# snc98_3x4_Switch-futuba.net
KiCad netlist of a schematic drawn in EAGLE
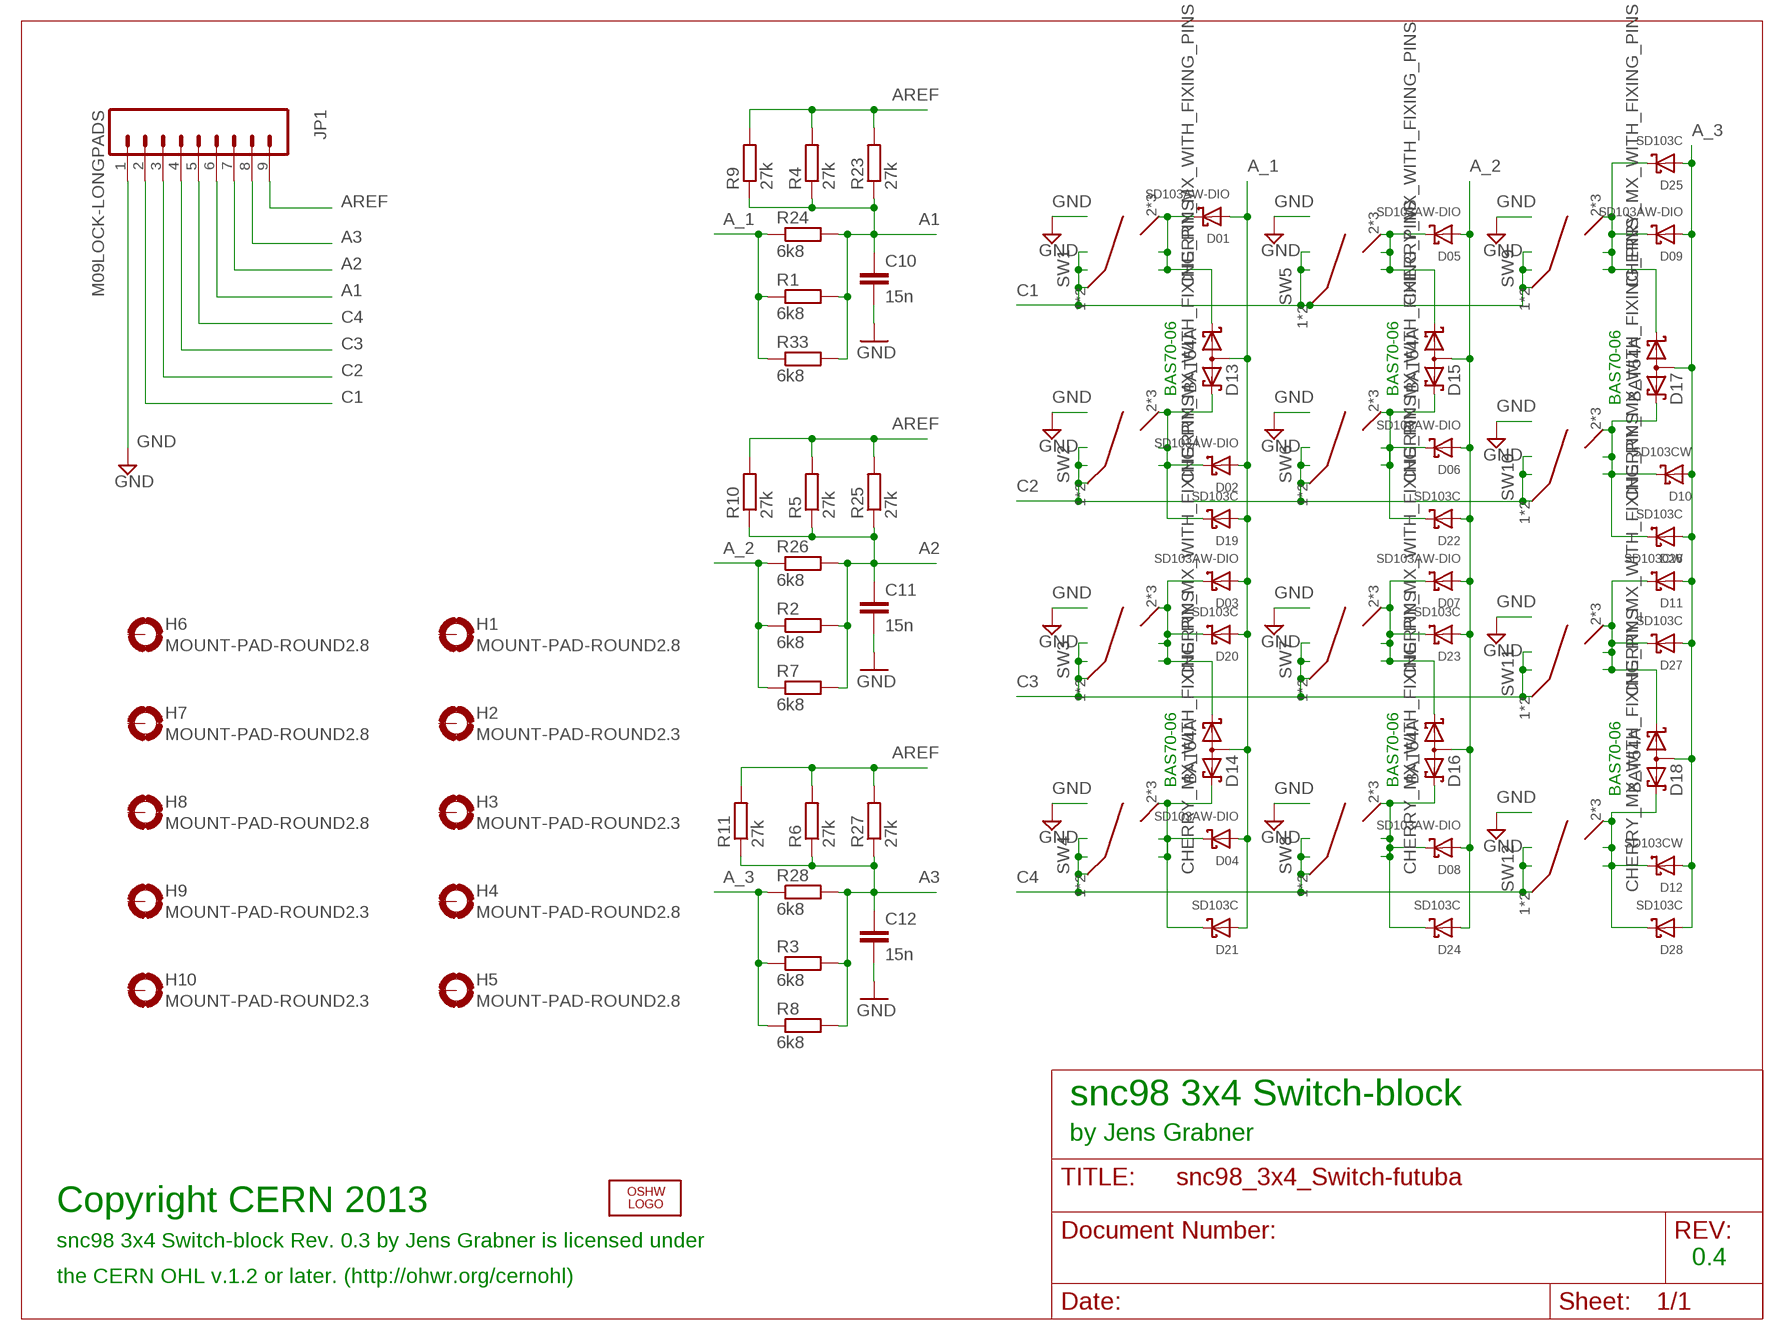
[diagram p0: schematic, sheet 1]

(export (version "E")
  (design (tool "Eeschema 10.0.6"))
  (components
    (comp (ref "C10")
      (value "15n")
      (footprint "eagle-import:C1206K")
      (libsource (lib "eagle-import") (part "C-EUC1206K"))
    )
    (comp (ref "C11")
      (value "15n")
      (footprint "eagle-import:C1206K")
      (libsource (lib "eagle-import") (part "C-EUC1206K"))
    )
    (comp (ref "C12")
      (value "15n")
      (footprint "eagle-import:C1206K")
      (libsource (lib "eagle-import") (part "C-EUC1206K"))
    )
    (comp (ref "D01")
      (value "SD103AW-DIO")
      (footprint "eagle-import:SOD-123F")
      (fields (field (name "MF") "MULTICOMP") (field (name "MPN") "SD103CW-7-F"))
      (libsource (lib "eagle-import") (part "DIODESOD-123F"))
    )
    (comp (ref "D02")
      (value "SD103AW-DIO")
      (footprint "eagle-import:SOD-123F")
      (fields (field (name "MF") "MULTICOMP") (field (name "MPN") "SD103CW-7-F"))
      (libsource (lib "eagle-import") (part "DIODESOD-123F"))
    )
    (comp (ref "D03")
      (value "SD103AW-DIO")
      (footprint "eagle-import:SOD-123F")
      (fields (field (name "MF") "MULTICOMP") (field (name "MPN") "SD103CW-7-F"))
      (libsource (lib "eagle-import") (part "DIODESOD-123F"))
    )
    (comp (ref "D04")
      (value "SD103AW-DIO")
      (footprint "eagle-import:SOD-123F")
      (fields (field (name "MF") "MULTICOMP") (field (name "MPN") "SD103CW-7-F"))
      (libsource (lib "eagle-import") (part "DIODESOD-123F"))
    )
    (comp (ref "D05")
      (value "SD103AW-DIO")
      (footprint "eagle-import:SOD-123F")
      (fields (field (name "MF") "MULTICOMP") (field (name "MPN") "SD103CW-7-F"))
      (libsource (lib "eagle-import") (part "DIODESOD-123F"))
    )
    (comp (ref "D06")
      (value "SD103AW-DIO")
      (footprint "eagle-import:SOD-123F")
      (fields (field (name "MF") "MULTICOMP") (field (name "MPN") "SD103CW-7-F"))
      (libsource (lib "eagle-import") (part "DIODESOD-123F"))
    )
    (comp (ref "D07")
      (value "SD103AW-DIO")
      (footprint "eagle-import:SOD-123F")
      (fields (field (name "MF") "MULTICOMP") (field (name "MPN") "SD103CW-7-F"))
      (libsource (lib "eagle-import") (part "DIODESOD-123F"))
    )
    (comp (ref "D08")
      (value "SD103AW-DIO")
      (footprint "eagle-import:SOD-123F")
      (fields (field (name "MF") "MULTICOMP") (field (name "MPN") "SD103CW-7-F"))
      (libsource (lib "eagle-import") (part "DIODESOD-123F"))
    )
    (comp (ref "D09")
      (value "SD103AW-DIO")
      (footprint "eagle-import:SOD-123F")
      (fields (field (name "MF") "MULTICOMP") (field (name "MPN") "SD103CW-7-F"))
      (libsource (lib "eagle-import") (part "DIODESOD-123F"))
    )
    (comp (ref "D10")
      (value "SD103CW")
      (footprint "eagle-import:SOD-123F")
      (fields (field (name "MF") "MULTICOMP") (field (name "MPN") "SD103CW-7-F"))
      (libsource (lib "eagle-import") (part "DIODESOD-123F"))
    )
    (comp (ref "D11")
      (value "SD103CW")
      (footprint "eagle-import:SOD-123F")
      (fields (field (name "MF") "MULTICOMP") (field (name "MPN") "SD103CW-7-F"))
      (libsource (lib "eagle-import") (part "DIODESOD-123F"))
    )
    (comp (ref "D12")
      (value "SD103CW")
      (footprint "eagle-import:SOD-123F")
      (fields (field (name "MF") "MULTICOMP") (field (name "MPN") "SD103CW-7-F"))
      (libsource (lib "eagle-import") (part "DIODESOD-123F"))
    )
    (comp (ref "D13")
      (value "BAT54A")
      (footprint "eagle-import:SOT23")
      (libsource (lib "eagle-import") (part "BAT54A"))
    )
    (comp (ref "D14")
      (value "BAT54A")
      (footprint "eagle-import:SOT23")
      (libsource (lib "eagle-import") (part "BAT54A"))
    )
    (comp (ref "D15")
      (value "BAT54A")
      (footprint "eagle-import:SOT23")
      (libsource (lib "eagle-import") (part "BAT54A"))
    )
    (comp (ref "D16")
      (value "BAT54A")
      (footprint "eagle-import:SOT23")
      (libsource (lib "eagle-import") (part "BAT54A"))
    )
    (comp (ref "D17")
      (value "BAT54A")
      (footprint "eagle-import:SOT23")
      (libsource (lib "eagle-import") (part "BAT54A"))
    )
    (comp (ref "D18")
      (value "BAT54A")
      (footprint "eagle-import:SOT23")
      (libsource (lib "eagle-import") (part "BAT54A"))
    )
    (comp (ref "D19")
      (value "SD103C")
      (footprint "eagle-import:280MIL-TH")
      (fields (field (name "MF") "MULTICOMP") (field (name "MPN") "SD103CW-7-F"))
      (libsource (lib "eagle-import") (part "DIODE280MIL-TH"))
    )
    (comp (ref "D20")
      (value "SD103C")
      (footprint "eagle-import:280MIL-TH")
      (fields (field (name "MF") "MULTICOMP") (field (name "MPN") "SD103CW-7-F"))
      (libsource (lib "eagle-import") (part "DIODE280MIL-TH"))
    )
    (comp (ref "D21")
      (value "SD103C")
      (footprint "eagle-import:280MIL-TH")
      (fields (field (name "MF") "MULTICOMP") (field (name "MPN") "SD103CW-7-F"))
      (libsource (lib "eagle-import") (part "DIODE280MIL-TH"))
    )
    (comp (ref "D22")
      (value "SD103C")
      (footprint "eagle-import:280MIL-TH")
      (fields (field (name "MF") "MULTICOMP") (field (name "MPN") "SD103CW-7-F"))
      (libsource (lib "eagle-import") (part "DIODE280MIL-TH"))
    )
    (comp (ref "D23")
      (value "SD103C")
      (footprint "eagle-import:280MIL-TH")
      (fields (field (name "MF") "MULTICOMP") (field (name "MPN") "SD103CW-7-F"))
      (libsource (lib "eagle-import") (part "DIODE280MIL-TH"))
    )
    (comp (ref "D24")
      (value "SD103C")
      (footprint "eagle-import:280MIL-TH")
      (fields (field (name "MF") "MULTICOMP") (field (name "MPN") "SD103CW-7-F"))
      (libsource (lib "eagle-import") (part "DIODE280MIL-TH"))
    )
    (comp (ref "D25")
      (value "SD103C")
      (footprint "eagle-import:280MIL-TH")
      (fields (field (name "MF") "MULTICOMP") (field (name "MPN") "SD103CW-7-F"))
      (libsource (lib "eagle-import") (part "DIODE280MIL-TH"))
    )
    (comp (ref "D26")
      (value "SD103C")
      (footprint "eagle-import:280MIL-TH")
      (fields (field (name "MF") "MULTICOMP") (field (name "MPN") "SD103CW-7-F"))
      (libsource (lib "eagle-import") (part "DIODE280MIL-TH"))
    )
    (comp (ref "D27")
      (value "SD103C")
      (footprint "eagle-import:280MIL-TH")
      (fields (field (name "MF") "MULTICOMP") (field (name "MPN") "SD103CW-7-F"))
      (libsource (lib "eagle-import") (part "DIODE280MIL-TH"))
    )
    (comp (ref "D28")
      (value "SD103C")
      (footprint "eagle-import:280MIL-TH")
      (fields (field (name "MF") "MULTICOMP") (field (name "MPN") "SD103CW-7-F"))
      (libsource (lib "eagle-import") (part "DIODE280MIL-TH"))
    )
    (comp (ref "H1")
      (value "MOUNT-PAD-ROUND2.8")
      (footprint "eagle-import:2,8-PAD")
      (libsource (lib "eagle-import") (part "MOUNT-PAD-ROUND2.8"))
    )
    (comp (ref "H2")
      (value "MOUNT-PAD-ROUND2.3")
      (footprint "eagle-import:2,3-PAD")
      (libsource (lib "eagle-import") (part "MOUNT-PAD-ROUND2.3"))
    )
    (comp (ref "H3")
      (value "MOUNT-PAD-ROUND2.3")
      (footprint "eagle-import:2,3-PAD")
      (libsource (lib "eagle-import") (part "MOUNT-PAD-ROUND2.3"))
    )
    (comp (ref "H4")
      (value "MOUNT-PAD-ROUND2.8")
      (footprint "eagle-import:2,8-PAD")
      (libsource (lib "eagle-import") (part "MOUNT-PAD-ROUND2.8"))
    )
    (comp (ref "H5")
      (value "MOUNT-PAD-ROUND2.8")
      (footprint "eagle-import:2,8-PAD")
      (libsource (lib "eagle-import") (part "MOUNT-PAD-ROUND2.8"))
    )
    (comp (ref "H6")
      (value "MOUNT-PAD-ROUND2.8")
      (footprint "eagle-import:2,8-PAD")
      (libsource (lib "eagle-import") (part "MOUNT-PAD-ROUND2.8"))
    )
    (comp (ref "H7")
      (value "MOUNT-PAD-ROUND2.8")
      (footprint "eagle-import:2,8-PAD")
      (libsource (lib "eagle-import") (part "MOUNT-PAD-ROUND2.8"))
    )
    (comp (ref "H8")
      (value "MOUNT-PAD-ROUND2.8")
      (footprint "eagle-import:2,8-PAD")
      (libsource (lib "eagle-import") (part "MOUNT-PAD-ROUND2.8"))
    )
    (comp (ref "H9")
      (value "MOUNT-PAD-ROUND2.3")
      (footprint "eagle-import:2,3-PAD")
      (libsource (lib "eagle-import") (part "MOUNT-PAD-ROUND2.3"))
    )
    (comp (ref "H10")
      (value "MOUNT-PAD-ROUND2.3")
      (footprint "eagle-import:2,3-PAD")
      (libsource (lib "eagle-import") (part "MOUNT-PAD-ROUND2.3"))
    )
    (comp (ref "JP1")
      (value "M09LOCK-LONGPADS")
      (footprint "eagle-import:1X09_LOCK_LONGPADS")
      (libsource (lib "eagle-import") (part "M09LOCK-LONGPADS"))
    )
    (comp (ref "LOGO1")
      (value "OSHW_LOGO_8MILX0150-NT")
      (footprint "eagle-import:OSHW_8X150_NOTEXT")
      (libsource (lib "eagle-import") (part "OSHW_LOGO_8MILX0150-NT"))
    )
    (comp (ref "R1")
      (value "6k8")
      (footprint "eagle-import:R1206")
      (libsource (lib "eagle-import") (part "R-EU_R1206"))
    )
    (comp (ref "R2")
      (value "6k8")
      (footprint "eagle-import:R1206")
      (libsource (lib "eagle-import") (part "R-EU_R1206"))
    )
    (comp (ref "R3")
      (value "6k8")
      (footprint "eagle-import:R1206")
      (libsource (lib "eagle-import") (part "R-EU_R1206"))
    )
    (comp (ref "R4")
      (value "27k")
      (footprint "eagle-import:R1206")
      (libsource (lib "eagle-import") (part "R-EU_R1206"))
    )
    (comp (ref "R5")
      (value "27k")
      (footprint "eagle-import:R1206")
      (libsource (lib "eagle-import") (part "R-EU_R1206"))
    )
    (comp (ref "R6")
      (value "27k")
      (footprint "eagle-import:R1206")
      (libsource (lib "eagle-import") (part "R-EU_R1206"))
    )
    (comp (ref "R7")
      (value "6k8")
      (footprint "eagle-import:M0805")
      (libsource (lib "eagle-import") (part "R-EU_M0805"))
    )
    (comp (ref "R8")
      (value "6k8")
      (footprint "eagle-import:M0805")
      (libsource (lib "eagle-import") (part "R-EU_M0805"))
    )
    (comp (ref "R9")
      (value "27k")
      (footprint "eagle-import:M0805")
      (libsource (lib "eagle-import") (part "R-EU_M0805"))
    )
    (comp (ref "R10")
      (value "27k")
      (footprint "eagle-import:M0805")
      (libsource (lib "eagle-import") (part "R-EU_M0805"))
    )
    (comp (ref "R11")
      (value "27k")
      (footprint "eagle-import:M0805")
      (libsource (lib "eagle-import") (part "R-EU_M0805"))
    )
    (comp (ref "R23")
      (value "27k")
      (footprint "eagle-import:0204_5")
      (libsource (lib "eagle-import") (part "R-EU_0204/5"))
    )
    (comp (ref "R24")
      (value "6k8")
      (footprint "eagle-import:0204_5")
      (libsource (lib "eagle-import") (part "R-EU_0204/5"))
    )
    (comp (ref "R25")
      (value "27k")
      (footprint "eagle-import:0204_5")
      (libsource (lib "eagle-import") (part "R-EU_0204/5"))
    )
    (comp (ref "R26")
      (value "6k8")
      (footprint "eagle-import:0204_5")
      (libsource (lib "eagle-import") (part "R-EU_0204/5"))
    )
    (comp (ref "R27")
      (value "27k")
      (footprint "eagle-import:0204_5")
      (libsource (lib "eagle-import") (part "R-EU_0204/5"))
    )
    (comp (ref "R28")
      (value "6k8")
      (footprint "eagle-import:0204_5")
      (libsource (lib "eagle-import") (part "R-EU_0204/5"))
    )
    (comp (ref "R33")
      (value "6k8")
      (footprint "eagle-import:M0805")
      (libsource (lib "eagle-import") (part "R-EU_M0805"))
    )
    (comp (ref "SW1")
      (value "CHERRY_MX_WITH_FIXING_PINS")
      (footprint "eagle-import:MX1A-XXNW")
      (libsource (lib "eagle-import") (part "CHERRY_MX_WITH_FIXING_PINS"))
    )
    (comp (ref "SW2")
      (value "CHERRY_MX_WITH_FIXING_PINS")
      (footprint "eagle-import:MX1A-XXNW")
      (libsource (lib "eagle-import") (part "CHERRY_MX_WITH_FIXING_PINS"))
    )
    (comp (ref "SW3")
      (value "CHERRY_MX_WITH_FIXING_PINS")
      (footprint "eagle-import:MX1A-XXNW")
      (libsource (lib "eagle-import") (part "CHERRY_MX_WITH_FIXING_PINS"))
    )
    (comp (ref "SW4")
      (value "CHERRY_MX_WITH_FIXING_PINS")
      (footprint "eagle-import:MX1A-XXNW")
      (libsource (lib "eagle-import") (part "CHERRY_MX_WITH_FIXING_PINS"))
    )
    (comp (ref "SW5")
      (value "CHERRY_MX_WITH_FIXING_PINS")
      (footprint "eagle-import:MX1A-XXNW")
      (libsource (lib "eagle-import") (part "CHERRY_MX_WITH_FIXING_PINS"))
    )
    (comp (ref "SW6")
      (value "CHERRY_MX_WITH_FIXING_PINS")
      (footprint "eagle-import:MX1A-XXNW")
      (libsource (lib "eagle-import") (part "CHERRY_MX_WITH_FIXING_PINS"))
    )
    (comp (ref "SW7")
      (value "CHERRY_MX_WITH_FIXING_PINS")
      (footprint "eagle-import:MX1A-XXNW")
      (libsource (lib "eagle-import") (part "CHERRY_MX_WITH_FIXING_PINS"))
    )
    (comp (ref "SW8")
      (value "CHERRY_MX_WITH_FIXING_PINS")
      (footprint "eagle-import:MX1A-XXNW")
      (libsource (lib "eagle-import") (part "CHERRY_MX_WITH_FIXING_PINS"))
    )
    (comp (ref "SW9")
      (value "CHERRY_MX_WITH_FIXING_PINS")
      (footprint "eagle-import:MX1A-XXNW")
      (libsource (lib "eagle-import") (part "CHERRY_MX_WITH_FIXING_PINS"))
    )
    (comp (ref "SW10")
      (value "CHERRY_MX_WITH_FIXING_PINS")
      (footprint "eagle-import:MX1A-XXNW")
      (libsource (lib "eagle-import") (part "CHERRY_MX_WITH_FIXING_PINS"))
    )
    (comp (ref "SW11")
      (value "CHERRY_MX_WITH_FIXING_PINS")
      (footprint "eagle-import:MX1A-XXNW")
      (libsource (lib "eagle-import") (part "CHERRY_MX_WITH_FIXING_PINS"))
    )
    (comp (ref "SW12")
      (value "CHERRY_MX_WITH_FIXING_PINS")
      (footprint "eagle-import:MX1A-XXNW")
      (libsource (lib "eagle-import") (part "CHERRY_MX_WITH_FIXING_PINS"))
    )
  )
  (nets
    (net (code "1") (name "/A1") (class "Default")
      (node (ref "C10") (pin "1") (pinfunction "1_1") (pintype "passive"))
      (node (ref "JP1") (pin "6") (pinfunction "6_6") (pintype "passive"))
      (node (ref "R1") (pin "2") (pinfunction "2_2") (pintype "passive"))
      (node (ref "R23") (pin "1") (pinfunction "1_1") (pintype "passive"))
      (node (ref "R24") (pin "2") (pinfunction "2_2") (pintype "passive"))
      (node (ref "R33") (pin "2") (pinfunction "2_2") (pintype "passive"))
      (node (ref "R4") (pin "1") (pinfunction "1_1") (pintype "passive"))
      (node (ref "R9") (pin "1") (pinfunction "1_1") (pintype "passive"))
    )
    (net (code "2") (name "/A2") (class "Default")
      (node (ref "C11") (pin "1") (pinfunction "1_1") (pintype "passive"))
      (node (ref "JP1") (pin "7") (pinfunction "7_7") (pintype "passive"))
      (node (ref "R10") (pin "1") (pinfunction "1_1") (pintype "passive"))
      (node (ref "R2") (pin "2") (pinfunction "2_2") (pintype "passive"))
      (node (ref "R25") (pin "1") (pinfunction "1_1") (pintype "passive"))
      (node (ref "R26") (pin "2") (pinfunction "2_2") (pintype "passive"))
      (node (ref "R5") (pin "1") (pinfunction "1_1") (pintype "passive"))
      (node (ref "R7") (pin "2") (pinfunction "2_2") (pintype "passive"))
    )
    (net (code "3") (name "/A3") (class "Default")
      (node (ref "C12") (pin "1") (pinfunction "1_1") (pintype "passive"))
      (node (ref "JP1") (pin "8") (pinfunction "8_8") (pintype "passive"))
      (node (ref "R11") (pin "1") (pinfunction "1_1") (pintype "passive"))
      (node (ref "R27") (pin "1") (pinfunction "1_1") (pintype "passive"))
      (node (ref "R28") (pin "2") (pinfunction "2_2") (pintype "passive"))
      (node (ref "R3") (pin "2") (pinfunction "2_2") (pintype "passive"))
      (node (ref "R6") (pin "1") (pinfunction "1_1") (pintype "passive"))
      (node (ref "R8") (pin "2") (pinfunction "2_2") (pintype "passive"))
    )
    (net (code "4") (name "/AREF") (class "Default")
      (node (ref "JP1") (pin "9") (pinfunction "9_9") (pintype "passive"))
      (node (ref "R10") (pin "2") (pinfunction "2_2") (pintype "passive"))
      (node (ref "R11") (pin "2") (pinfunction "2_2") (pintype "passive"))
      (node (ref "R23") (pin "2") (pinfunction "2_2") (pintype "passive"))
      (node (ref "R25") (pin "2") (pinfunction "2_2") (pintype "passive"))
      (node (ref "R27") (pin "2") (pinfunction "2_2") (pintype "passive"))
      (node (ref "R4") (pin "2") (pinfunction "2_2") (pintype "passive"))
      (node (ref "R5") (pin "2") (pinfunction "2_2") (pintype "passive"))
      (node (ref "R6") (pin "2") (pinfunction "2_2") (pintype "passive"))
      (node (ref "R9") (pin "2") (pinfunction "2_2") (pintype "passive"))
    )
    (net (code "5") (name "/A_1") (class "Default")
      (node (ref "D01") (pin "A") (pinfunction "A_A") (pintype "passive"))
      (node (ref "D02") (pin "A") (pinfunction "A_A") (pintype "passive"))
      (node (ref "D03") (pin "A") (pinfunction "A_A") (pintype "passive"))
      (node (ref "D04") (pin "A") (pinfunction "A_A") (pintype "passive"))
      (node (ref "D13") (pin "3") (pinfunction "AA_3") (pintype "passive"))
      (node (ref "D14") (pin "3") (pinfunction "AA_3") (pintype "passive"))
      (node (ref "D19") (pin "P$1") (pinfunction "A_P$1") (pintype "passive"))
      (node (ref "D20") (pin "P$1") (pinfunction "A_P$1") (pintype "passive"))
      (node (ref "D21") (pin "P$1") (pinfunction "A_P$1") (pintype "passive"))
      (node (ref "R1") (pin "1") (pinfunction "1_1") (pintype "passive"))
      (node (ref "R24") (pin "1") (pinfunction "1_1") (pintype "passive"))
      (node (ref "R33") (pin "1") (pinfunction "1_1") (pintype "passive"))
    )
    (net (code "6") (name "/A_2") (class "Default")
      (node (ref "D05") (pin "A") (pinfunction "A_A") (pintype "passive"))
      (node (ref "D06") (pin "A") (pinfunction "A_A") (pintype "passive"))
      (node (ref "D07") (pin "A") (pinfunction "A_A") (pintype "passive"))
      (node (ref "D08") (pin "A") (pinfunction "A_A") (pintype "passive"))
      (node (ref "D15") (pin "3") (pinfunction "AA_3") (pintype "passive"))
      (node (ref "D16") (pin "3") (pinfunction "AA_3") (pintype "passive"))
      (node (ref "D22") (pin "P$1") (pinfunction "A_P$1") (pintype "passive"))
      (node (ref "D23") (pin "P$1") (pinfunction "A_P$1") (pintype "passive"))
      (node (ref "D24") (pin "P$1") (pinfunction "A_P$1") (pintype "passive"))
      (node (ref "R2") (pin "1") (pinfunction "1_1") (pintype "passive"))
      (node (ref "R26") (pin "1") (pinfunction "1_1") (pintype "passive"))
      (node (ref "R7") (pin "1") (pinfunction "1_1") (pintype "passive"))
    )
    (net (code "7") (name "/A_3") (class "Default")
      (node (ref "D09") (pin "A") (pinfunction "A_A") (pintype "passive"))
      (node (ref "D10") (pin "A") (pinfunction "A_A") (pintype "passive"))
      (node (ref "D11") (pin "A") (pinfunction "A_A") (pintype "passive"))
      (node (ref "D12") (pin "A") (pinfunction "A_A") (pintype "passive"))
      (node (ref "D17") (pin "3") (pinfunction "AA_3") (pintype "passive"))
      (node (ref "D18") (pin "3") (pinfunction "AA_3") (pintype "passive"))
      (node (ref "D25") (pin "P$1") (pinfunction "A_P$1") (pintype "passive"))
      (node (ref "D26") (pin "P$1") (pinfunction "A_P$1") (pintype "passive"))
      (node (ref "D27") (pin "P$1") (pinfunction "A_P$1") (pintype "passive"))
      (node (ref "D28") (pin "P$1") (pinfunction "A_P$1") (pintype "passive"))
      (node (ref "R28") (pin "1") (pinfunction "1_1") (pintype "passive"))
      (node (ref "R3") (pin "1") (pinfunction "1_1") (pintype "passive"))
      (node (ref "R8") (pin "1") (pinfunction "1_1") (pintype "passive"))
    )
    (net (code "8") (name "/C1") (class "Default")
      (node (ref "JP1") (pin "2") (pinfunction "2_2") (pintype "passive"))
      (node (ref "SW1") (pin "1") (pinfunction "1_1") (pintype "passive"))
      (node (ref "SW1") (pin "3") (pinfunction "1_3") (pintype "passive"))
      (node (ref "SW5") (pin "1") (pinfunction "1_1") (pintype "passive"))
      (node (ref "SW5") (pin "3") (pinfunction "1_3") (pintype "passive"))
      (node (ref "SW9") (pin "1") (pinfunction "1_1") (pintype "passive"))
      (node (ref "SW9") (pin "3") (pinfunction "1_3") (pintype "passive"))
    )
    (net (code "9") (name "/C2") (class "Default")
      (node (ref "JP1") (pin "3") (pinfunction "3_3") (pintype "passive"))
      (node (ref "SW10") (pin "1") (pinfunction "1_1") (pintype "passive"))
      (node (ref "SW10") (pin "3") (pinfunction "1_3") (pintype "passive"))
      (node (ref "SW2") (pin "1") (pinfunction "1_1") (pintype "passive"))
      (node (ref "SW2") (pin "3") (pinfunction "1_3") (pintype "passive"))
      (node (ref "SW6") (pin "1") (pinfunction "1_1") (pintype "passive"))
      (node (ref "SW6") (pin "3") (pinfunction "1_3") (pintype "passive"))
    )
    (net (code "10") (name "/C3") (class "Default")
      (node (ref "JP1") (pin "4") (pinfunction "4_4") (pintype "passive"))
      (node (ref "SW11") (pin "1") (pinfunction "1_1") (pintype "passive"))
      (node (ref "SW11") (pin "3") (pinfunction "1_3") (pintype "passive"))
      (node (ref "SW3") (pin "1") (pinfunction "1_1") (pintype "passive"))
      (node (ref "SW3") (pin "3") (pinfunction "1_3") (pintype "passive"))
      (node (ref "SW7") (pin "1") (pinfunction "1_1") (pintype "passive"))
      (node (ref "SW7") (pin "3") (pinfunction "1_3") (pintype "passive"))
    )
    (net (code "11") (name "/C4") (class "Default")
      (node (ref "JP1") (pin "5") (pinfunction "5_5") (pintype "passive"))
      (node (ref "SW12") (pin "1") (pinfunction "1_1") (pintype "passive"))
      (node (ref "SW12") (pin "3") (pinfunction "1_3") (pintype "passive"))
      (node (ref "SW4") (pin "1") (pinfunction "1_1") (pintype "passive"))
      (node (ref "SW4") (pin "3") (pinfunction "1_3") (pintype "passive"))
      (node (ref "SW8") (pin "1") (pinfunction "1_1") (pintype "passive"))
      (node (ref "SW8") (pin "3") (pinfunction "1_3") (pintype "passive"))
    )
    (net (code "12") (name "GND") (class "Default")
      (node (ref "C10") (pin "2") (pinfunction "2_2") (pintype "passive"))
      (node (ref "C11") (pin "2") (pinfunction "2_2") (pintype "passive"))
      (node (ref "C12") (pin "2") (pinfunction "2_2") (pintype "passive"))
      (node (ref "JP1") (pin "1") (pinfunction "1_1") (pintype "passive"))
    )
    (net (code "13") (name "Net-(D13-K1)") (class "Default")
      (node (ref "D01") (pin "C") (pinfunction "C_C") (pintype "passive"))
      (node (ref "D13") (pin "1") (pinfunction "K1_1") (pintype "passive"))
      (node (ref "SW1") (pin "2") (pinfunction "2_2") (pintype "passive"))
      (node (ref "SW1") (pin "4") (pinfunction "2_4") (pintype "passive"))
      (node (ref "SW1") (pin "5") (pinfunction "2_5") (pintype "passive"))
    )
    (net (code "14") (name "Net-(D13-K2)") (class "Default")
      (node (ref "D02") (pin "C") (pinfunction "C_C") (pintype "passive"))
      (node (ref "D13") (pin "2") (pinfunction "K2_2") (pintype "passive"))
      (node (ref "D19") (pin "P$2") (pinfunction "C_P$2") (pintype "passive"))
      (node (ref "SW2") (pin "2") (pinfunction "2_2") (pintype "passive"))
      (node (ref "SW2") (pin "4") (pinfunction "2_4") (pintype "passive"))
      (node (ref "SW2") (pin "5") (pinfunction "2_5") (pintype "passive"))
    )
    (net (code "15") (name "Net-(D14-K1)") (class "Default")
      (node (ref "D03") (pin "C") (pinfunction "C_C") (pintype "passive"))
      (node (ref "D14") (pin "1") (pinfunction "K1_1") (pintype "passive"))
      (node (ref "D20") (pin "P$2") (pinfunction "C_P$2") (pintype "passive"))
      (node (ref "SW3") (pin "2") (pinfunction "2_2") (pintype "passive"))
      (node (ref "SW3") (pin "4") (pinfunction "2_4") (pintype "passive"))
      (node (ref "SW3") (pin "5") (pinfunction "2_5") (pintype "passive"))
    )
    (net (code "16") (name "Net-(D14-K2)") (class "Default")
      (node (ref "D04") (pin "C") (pinfunction "C_C") (pintype "passive"))
      (node (ref "D14") (pin "2") (pinfunction "K2_2") (pintype "passive"))
      (node (ref "D21") (pin "P$2") (pinfunction "C_P$2") (pintype "passive"))
      (node (ref "SW4") (pin "2") (pinfunction "2_2") (pintype "passive"))
      (node (ref "SW4") (pin "4") (pinfunction "2_4") (pintype "passive"))
      (node (ref "SW4") (pin "5") (pinfunction "2_5") (pintype "passive"))
    )
    (net (code "17") (name "Net-(D15-K1)") (class "Default")
      (node (ref "D05") (pin "C") (pinfunction "C_C") (pintype "passive"))
      (node (ref "D15") (pin "1") (pinfunction "K1_1") (pintype "passive"))
      (node (ref "SW5") (pin "2") (pinfunction "2_2") (pintype "passive"))
      (node (ref "SW5") (pin "4") (pinfunction "2_4") (pintype "passive"))
      (node (ref "SW5") (pin "5") (pinfunction "2_5") (pintype "passive"))
    )
    (net (code "18") (name "Net-(D15-K2)") (class "Default")
      (node (ref "D06") (pin "C") (pinfunction "C_C") (pintype "passive"))
      (node (ref "D15") (pin "2") (pinfunction "K2_2") (pintype "passive"))
      (node (ref "D22") (pin "P$2") (pinfunction "C_P$2") (pintype "passive"))
      (node (ref "SW6") (pin "2") (pinfunction "2_2") (pintype "passive"))
      (node (ref "SW6") (pin "4") (pinfunction "2_4") (pintype "passive"))
      (node (ref "SW6") (pin "5") (pinfunction "2_5") (pintype "passive"))
    )
    (net (code "19") (name "Net-(D16-K1)") (class "Default")
      (node (ref "D07") (pin "C") (pinfunction "C_C") (pintype "passive"))
      (node (ref "D16") (pin "1") (pinfunction "K1_1") (pintype "passive"))
      (node (ref "D23") (pin "P$2") (pinfunction "C_P$2") (pintype "passive"))
      (node (ref "SW7") (pin "2") (pinfunction "2_2") (pintype "passive"))
      (node (ref "SW7") (pin "4") (pinfunction "2_4") (pintype "passive"))
      (node (ref "SW7") (pin "5") (pinfunction "2_5") (pintype "passive"))
    )
    (net (code "20") (name "Net-(D16-K2)") (class "Default")
      (node (ref "D08") (pin "C") (pinfunction "C_C") (pintype "passive"))
      (node (ref "D16") (pin "2") (pinfunction "K2_2") (pintype "passive"))
      (node (ref "D24") (pin "P$2") (pinfunction "C_P$2") (pintype "passive"))
      (node (ref "SW8") (pin "2") (pinfunction "2_2") (pintype "passive"))
      (node (ref "SW8") (pin "4") (pinfunction "2_4") (pintype "passive"))
      (node (ref "SW8") (pin "5") (pinfunction "2_5") (pintype "passive"))
    )
    (net (code "21") (name "Net-(D17-K1)") (class "Default")
      (node (ref "D09") (pin "C") (pinfunction "C_C") (pintype "passive"))
      (node (ref "D17") (pin "1") (pinfunction "K1_1") (pintype "passive"))
      (node (ref "D25") (pin "P$2") (pinfunction "C_P$2") (pintype "passive"))
      (node (ref "SW9") (pin "2") (pinfunction "2_2") (pintype "passive"))
      (node (ref "SW9") (pin "4") (pinfunction "2_4") (pintype "passive"))
      (node (ref "SW9") (pin "5") (pinfunction "2_5") (pintype "passive"))
    )
    (net (code "22") (name "Net-(D17-K2)") (class "Default")
      (node (ref "D10") (pin "C") (pinfunction "C_C") (pintype "passive"))
      (node (ref "D17") (pin "2") (pinfunction "K2_2") (pintype "passive"))
      (node (ref "D26") (pin "P$2") (pinfunction "C_P$2") (pintype "passive"))
      (node (ref "SW10") (pin "2") (pinfunction "2_2") (pintype "passive"))
      (node (ref "SW10") (pin "4") (pinfunction "2_4") (pintype "passive"))
      (node (ref "SW10") (pin "5") (pinfunction "2_5") (pintype "passive"))
    )
    (net (code "23") (name "Net-(D18-K1)") (class "Default")
      (node (ref "D11") (pin "C") (pinfunction "C_C") (pintype "passive"))
      (node (ref "D18") (pin "1") (pinfunction "K1_1") (pintype "passive"))
      (node (ref "D27") (pin "P$2") (pinfunction "C_P$2") (pintype "passive"))
      (node (ref "SW11") (pin "2") (pinfunction "2_2") (pintype "passive"))
      (node (ref "SW11") (pin "4") (pinfunction "2_4") (pintype "passive"))
      (node (ref "SW11") (pin "5") (pinfunction "2_5") (pintype "passive"))
    )
    (net (code "24") (name "Net-(D18-K2)") (class "Default")
      (node (ref "D12") (pin "C") (pinfunction "C_C") (pintype "passive"))
      (node (ref "D18") (pin "2") (pinfunction "K2_2") (pintype "passive"))
      (node (ref "D28") (pin "P$2") (pinfunction "C_P$2") (pintype "passive"))
      (node (ref "SW12") (pin "2") (pinfunction "2_2") (pintype "passive"))
      (node (ref "SW12") (pin "4") (pinfunction "2_4") (pintype "passive"))
      (node (ref "SW12") (pin "5") (pinfunction "2_5") (pintype "passive"))
    )
    (net (code "25") (name "unconnected-(H1-MOUNT-PadB2,8)") (class "Default")
      (node (ref "H1") (pin "B2,8") (pinfunction "MOUNT_B2,8") (pintype "passive"))
    )
    (net (code "26") (name "unconnected-(H2-MOUNT-PadB2,8)") (class "Default")
      (node (ref "H2") (pin "B2,8") (pinfunction "MOUNT_B2,8") (pintype "passive"))
    )
    (net (code "27") (name "unconnected-(H3-MOUNT-PadB2,8)") (class "Default")
      (node (ref "H3") (pin "B2,8") (pinfunction "MOUNT_B2,8") (pintype "passive"))
    )
    (net (code "28") (name "unconnected-(H4-MOUNT-PadB2,8)") (class "Default")
      (node (ref "H4") (pin "B2,8") (pinfunction "MOUNT_B2,8") (pintype "passive"))
    )
    (net (code "29") (name "unconnected-(H5-MOUNT-PadB2,8)") (class "Default")
      (node (ref "H5") (pin "B2,8") (pinfunction "MOUNT_B2,8") (pintype "passive"))
    )
    (net (code "30") (name "unconnected-(H6-MOUNT-PadB2,8)") (class "Default")
      (node (ref "H6") (pin "B2,8") (pinfunction "MOUNT_B2,8") (pintype "passive"))
    )
    (net (code "31") (name "unconnected-(H7-MOUNT-PadB2,8)") (class "Default")
      (node (ref "H7") (pin "B2,8") (pinfunction "MOUNT_B2,8") (pintype "passive"))
    )
    (net (code "32") (name "unconnected-(H8-MOUNT-PadB2,8)") (class "Default")
      (node (ref "H8") (pin "B2,8") (pinfunction "MOUNT_B2,8") (pintype "passive"))
    )
    (net (code "33") (name "unconnected-(H9-MOUNT-PadB2,8)") (class "Default")
      (node (ref "H9") (pin "B2,8") (pinfunction "MOUNT_B2,8") (pintype "passive"))
    )
    (net (code "34") (name "unconnected-(H10-MOUNT-PadB2,8)") (class "Default")
      (node (ref "H10") (pin "B2,8") (pinfunction "MOUNT_B2,8") (pintype "passive"))
    )
  )
)
